# BT121breakout.net
KiCad netlist of a schematic drawn in EAGLE
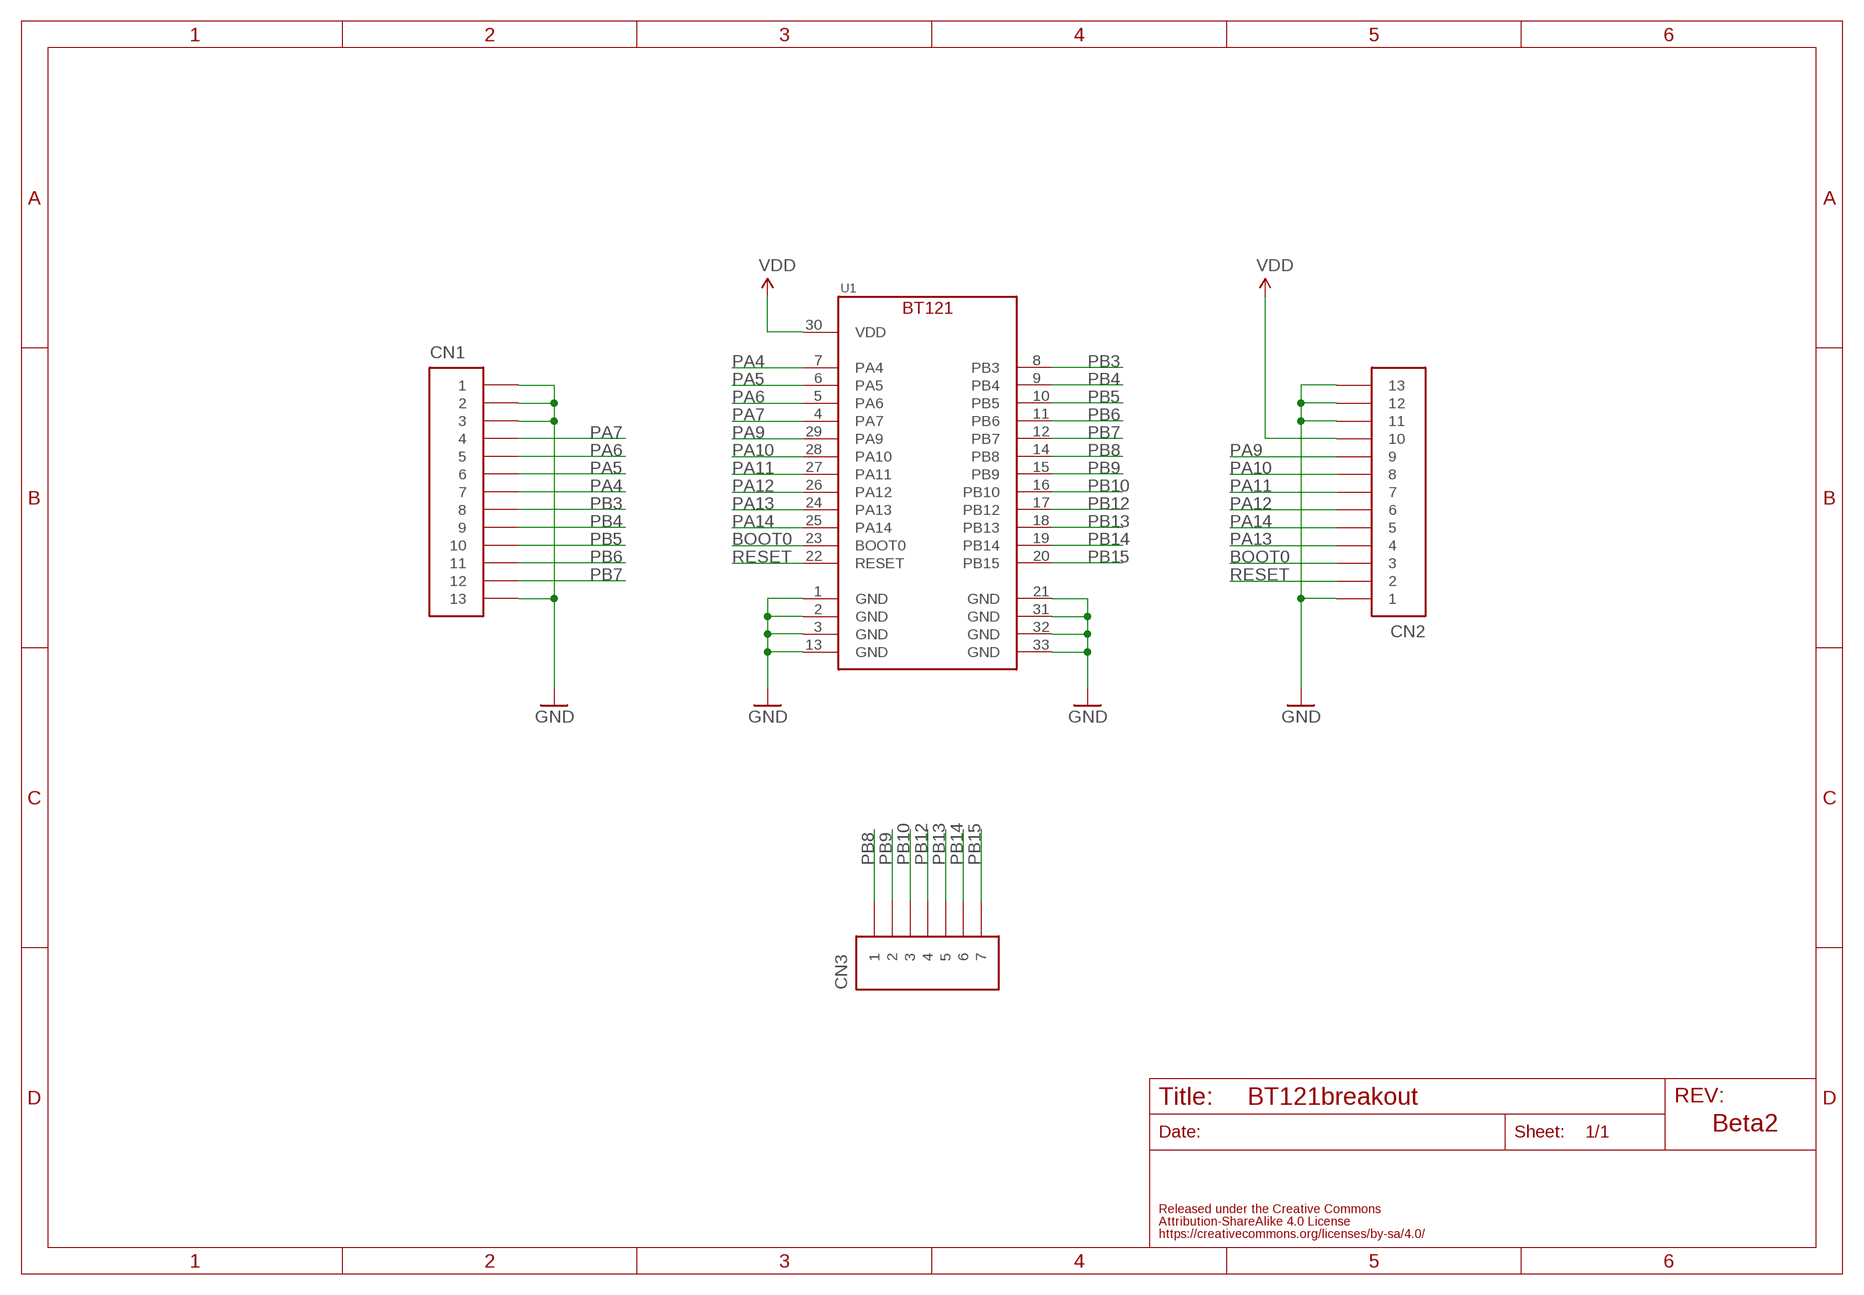
[diagram p0: schematic, sheet 1]

(export (version "E")
  (design (tool "Eeschema 10.0.6"))
  (components
    (comp (ref "CN1")
      (value "PIN_HEADER_1X13")
      (footprint "eagle-import:PIN_1X13")
      (libsource (lib "eagle-import") (part "PIN_HEADER_1X13"))
    )
    (comp (ref "CN2")
      (value "PIN_HEADER_1X13")
      (footprint "eagle-import:PIN_1X13")
      (libsource (lib "eagle-import") (part "PIN_HEADER_1X13"))
    )
    (comp (ref "CN3")
      (value "PIN_HEADER_1X7")
      (footprint "eagle-import:PIN_1X7")
      (libsource (lib "eagle-import") (part "PIN_HEADER_1X7"))
    )
    (comp (ref "U1")
      (value "SILICONLABS-BT121")
      (footprint "eagle-import:SILICONLABS-BT121")
      (libsource (lib "eagle-import") (part "SILICONLABS-BT121"))
    )
  )
  (nets
    (net (code "1") (name "/BOOT0") (class "Default")
      (node (ref "CN2") (pin "3") (pinfunction "3_3") (pintype "bidirectional"))
      (node (ref "U1") (pin "23") (pinfunction "BOOT0_23") (pintype "bidirectional"))
    )
    (net (code "2") (name "/PA4") (class "Default")
      (node (ref "CN1") (pin "7") (pinfunction "7_7") (pintype "bidirectional"))
      (node (ref "U1") (pin "7") (pinfunction "PA4_7") (pintype "bidirectional"))
    )
    (net (code "3") (name "/PA5") (class "Default")
      (node (ref "CN1") (pin "6") (pinfunction "6_6") (pintype "bidirectional"))
      (node (ref "U1") (pin "6") (pinfunction "PA5_6") (pintype "bidirectional"))
    )
    (net (code "4") (name "/PA6") (class "Default")
      (node (ref "CN1") (pin "5") (pinfunction "5_5") (pintype "bidirectional"))
      (node (ref "U1") (pin "5") (pinfunction "PA6_5") (pintype "bidirectional"))
    )
    (net (code "5") (name "/PA7") (class "Default")
      (node (ref "CN1") (pin "4") (pinfunction "4_4") (pintype "bidirectional"))
      (node (ref "U1") (pin "4") (pinfunction "PA7_4") (pintype "bidirectional"))
    )
    (net (code "6") (name "/PA9") (class "Default")
      (node (ref "CN2") (pin "9") (pinfunction "9_9") (pintype "bidirectional"))
      (node (ref "U1") (pin "29") (pinfunction "PA9_29") (pintype "bidirectional"))
    )
    (net (code "7") (name "/PA10") (class "Default")
      (node (ref "CN2") (pin "8") (pinfunction "8_8") (pintype "bidirectional"))
      (node (ref "U1") (pin "28") (pinfunction "PA10_28") (pintype "bidirectional"))
    )
    (net (code "8") (name "/PA11") (class "Default")
      (node (ref "CN2") (pin "7") (pinfunction "7_7") (pintype "bidirectional"))
      (node (ref "U1") (pin "27") (pinfunction "PA11_27") (pintype "bidirectional"))
    )
    (net (code "9") (name "/PA12") (class "Default")
      (node (ref "CN2") (pin "6") (pinfunction "6_6") (pintype "bidirectional"))
      (node (ref "U1") (pin "26") (pinfunction "PA12_26") (pintype "bidirectional"))
    )
    (net (code "10") (name "/PA13") (class "Default")
      (node (ref "CN2") (pin "4") (pinfunction "4_4") (pintype "bidirectional"))
      (node (ref "U1") (pin "24") (pinfunction "PA13_24") (pintype "bidirectional"))
    )
    (net (code "11") (name "/PA14") (class "Default")
      (node (ref "CN2") (pin "5") (pinfunction "5_5") (pintype "bidirectional"))
      (node (ref "U1") (pin "25") (pinfunction "PA14_25") (pintype "bidirectional"))
    )
    (net (code "12") (name "/PB3") (class "Default")
      (node (ref "CN1") (pin "8") (pinfunction "8_8") (pintype "bidirectional"))
      (node (ref "U1") (pin "8") (pinfunction "PB3_8") (pintype "bidirectional"))
    )
    (net (code "13") (name "/PB4") (class "Default")
      (node (ref "CN1") (pin "9") (pinfunction "9_9") (pintype "bidirectional"))
      (node (ref "U1") (pin "9") (pinfunction "PB4_9") (pintype "bidirectional"))
    )
    (net (code "14") (name "/PB5") (class "Default")
      (node (ref "CN1") (pin "10") (pinfunction "10_10") (pintype "bidirectional"))
      (node (ref "U1") (pin "10") (pinfunction "PB5_10") (pintype "bidirectional"))
    )
    (net (code "15") (name "/PB6") (class "Default")
      (node (ref "CN1") (pin "11") (pinfunction "11_11") (pintype "bidirectional"))
      (node (ref "U1") (pin "11") (pinfunction "PB6_11") (pintype "bidirectional"))
    )
    (net (code "16") (name "/PB7") (class "Default")
      (node (ref "CN1") (pin "12") (pinfunction "12_12") (pintype "bidirectional"))
      (node (ref "U1") (pin "12") (pinfunction "PB7_12") (pintype "bidirectional"))
    )
    (net (code "17") (name "/PB8") (class "Default")
      (node (ref "CN3") (pin "1") (pinfunction "1_1") (pintype "bidirectional"))
      (node (ref "U1") (pin "14") (pinfunction "PB8_14") (pintype "bidirectional"))
    )
    (net (code "18") (name "/PB9") (class "Default")
      (node (ref "CN3") (pin "2") (pinfunction "2_2") (pintype "bidirectional"))
      (node (ref "U1") (pin "15") (pinfunction "PB9_15") (pintype "bidirectional"))
    )
    (net (code "19") (name "/PB10") (class "Default")
      (node (ref "CN3") (pin "3") (pinfunction "3_3") (pintype "bidirectional"))
      (node (ref "U1") (pin "16") (pinfunction "PB10_16") (pintype "bidirectional"))
    )
    (net (code "20") (name "/PB12") (class "Default")
      (node (ref "CN3") (pin "4") (pinfunction "4_4") (pintype "bidirectional"))
      (node (ref "U1") (pin "17") (pinfunction "PB12_17") (pintype "bidirectional"))
    )
    (net (code "21") (name "/PB13") (class "Default")
      (node (ref "CN3") (pin "5") (pinfunction "5_5") (pintype "bidirectional"))
      (node (ref "U1") (pin "18") (pinfunction "PB13_18") (pintype "bidirectional"))
    )
    (net (code "22") (name "/PB14") (class "Default")
      (node (ref "CN3") (pin "6") (pinfunction "6_6") (pintype "bidirectional"))
      (node (ref "U1") (pin "19") (pinfunction "PB14_19") (pintype "bidirectional"))
    )
    (net (code "23") (name "/PB15") (class "Default")
      (node (ref "CN3") (pin "7") (pinfunction "7_7") (pintype "bidirectional"))
      (node (ref "U1") (pin "20") (pinfunction "PB15_20") (pintype "bidirectional"))
    )
    (net (code "24") (name "/RESET") (class "Default")
      (node (ref "CN2") (pin "2") (pinfunction "2_2") (pintype "bidirectional"))
      (node (ref "U1") (pin "22") (pinfunction "RESET_22") (pintype "bidirectional"))
    )
    (net (code "25") (name "GND") (class "Default")
      (node (ref "CN1") (pin "1") (pinfunction "1_1") (pintype "bidirectional"))
      (node (ref "CN1") (pin "13") (pinfunction "13_13") (pintype "bidirectional"))
      (node (ref "CN1") (pin "2") (pinfunction "2_2") (pintype "bidirectional"))
      (node (ref "CN1") (pin "3") (pinfunction "3_3") (pintype "bidirectional"))
      (node (ref "CN2") (pin "1") (pinfunction "1_1") (pintype "bidirectional"))
      (node (ref "CN2") (pin "11") (pinfunction "11_11") (pintype "bidirectional"))
      (node (ref "CN2") (pin "12") (pinfunction "12_12") (pintype "bidirectional"))
      (node (ref "CN2") (pin "13") (pinfunction "13_13") (pintype "bidirectional"))
      (node (ref "U1") (pin "1") (pinfunction "GND_1") (pintype "bidirectional"))
      (node (ref "U1") (pin "13") (pinfunction "GND_13") (pintype "bidirectional"))
      (node (ref "U1") (pin "2") (pinfunction "GND_2") (pintype "bidirectional"))
      (node (ref "U1") (pin "21") (pinfunction "GND_21") (pintype "bidirectional"))
      (node (ref "U1") (pin "3") (pinfunction "GND_3") (pintype "bidirectional"))
      (node (ref "U1") (pin "31") (pinfunction "GND_31") (pintype "bidirectional"))
      (node (ref "U1") (pin "32") (pinfunction "GND_32") (pintype "bidirectional"))
      (node (ref "U1") (pin "33") (pinfunction "GND_33") (pintype "bidirectional"))
    )
    (net (code "26") (name "VDD") (class "Default")
      (node (ref "CN2") (pin "10") (pinfunction "10_10") (pintype "bidirectional"))
      (node (ref "U1") (pin "30") (pinfunction "VDD_30") (pintype "bidirectional"))
    )
  )
)
